# moterdriver.net
KiCad netlist of a schematic drawn in Altium Designer
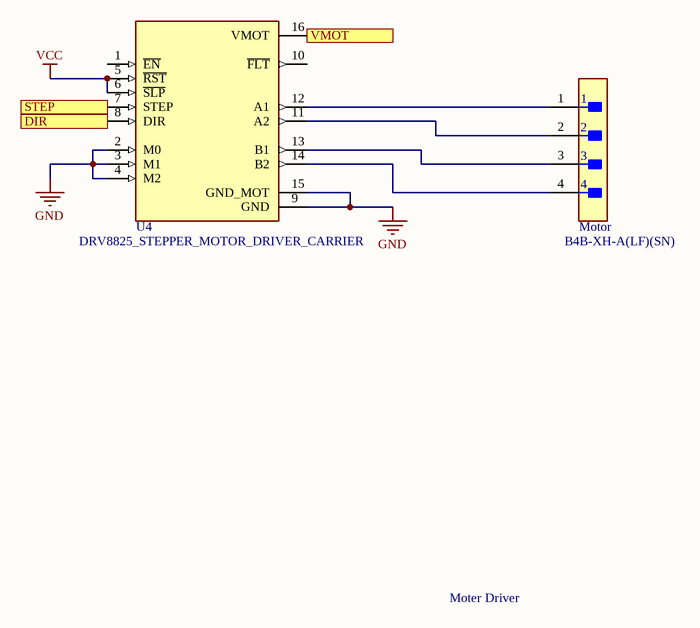
[diagram p0: moterdriver.SchDoc]

(export (version "E")
  (design (tool "Eeschema 10.0.6"))
  (components
    (comp (ref "Motor")
      (value "B4B-XH-A(LF)(SN)")
      (footprint "FP-B4B-XH-A_LF_SN-MFG")
      (description "CONN HEADER VERT 4POS 2.5MM")
      (libsource (lib "Altium Content Vault") (part "299a8cea1bdcbc3624fe62c390fa72c"))
    )
    (comp (ref "U4")
      (value "DRV8825_STEPPER_MOTOR_DRIVER_CARRIER")
      (footprint "IC_DRV8825_STEPPER_MOTOR_DRIVER_CARRIER")
      (description "Stepper motor controler; IC: DRV8825; 1.5A; Uin mot: 8.2Ã·45V")
      (libsource (lib "DRV8825_STEPPER_MOTOR_DRIVER_CARRIER") (part "DRV8825_STEPPER_MOTOR_DRIVER_CARRIER"))
    )
  )
  (nets
    (net (code "1") (name "/DIR") (class "Default")
      (node (ref "U4") (pin "8") (pinfunction "DIR_8") (pintype "input"))
    )
    (net (code "2") (name "/STEP") (class "Default")
      (node (ref "U4") (pin "7") (pinfunction "STEP_7") (pintype "input"))
    )
    (net (code "3") (name "/VMOT") (class "Default")
      (node (ref "U4") (pin "16") (pinfunction "VMOT_16") (pintype "power_in"))
    )
    (net (code "4") (name "GND") (class "Default")
      (node (ref "U4") (pin "15") (pinfunction "GND_MOT_15") (pintype "power_in"))
      (node (ref "U4") (pin "2") (pinfunction "M0_2") (pintype "input"))
      (node (ref "U4") (pin "3") (pinfunction "M1_3") (pintype "input"))
      (node (ref "U4") (pin "4") (pinfunction "M2_4") (pintype "input"))
      (node (ref "U4") (pin "9") (pinfunction "GND_9") (pintype "power_in"))
    )
    (net (code "5") (name "Net-(U4-A1)") (class "Default")
      (node (ref "Motor") (pin "1") (pinfunction "1_1") (pintype "passive"))
      (node (ref "U4") (pin "12") (pinfunction "A1_12") (pintype "output"))
    )
    (net (code "6") (name "Net-(U4-A2)") (class "Default")
      (node (ref "Motor") (pin "2") (pinfunction "2_2") (pintype "passive"))
      (node (ref "U4") (pin "11") (pinfunction "A2_11") (pintype "output"))
    )
    (net (code "7") (name "Net-(U4-B1)") (class "Default")
      (node (ref "Motor") (pin "3") (pinfunction "3_3") (pintype "passive"))
      (node (ref "U4") (pin "13") (pinfunction "B1_13") (pintype "output"))
    )
    (net (code "8") (name "Net-(U4-B2)") (class "Default")
      (node (ref "Motor") (pin "4") (pinfunction "4_4") (pintype "passive"))
      (node (ref "U4") (pin "14") (pinfunction "B2_14") (pintype "output"))
    )
    (net (code "9") (name "VCC") (class "Default")
      (node (ref "U4") (pin "5") (pinfunction "~{RST}_5") (pintype "input"))
      (node (ref "U4") (pin "6") (pinfunction "~{SLP}_6") (pintype "input"))
    )
    (net (code "10") (name "unconnected-(U4-~{EN}-Pad1)") (class "Default")
      (node (ref "U4") (pin "1") (pinfunction "~{EN}_1") (pintype "input"))
    )
    (net (code "11") (name "unconnected-(U4-~{FLT}-Pad10)") (class "Default")
      (node (ref "U4") (pin "10") (pinfunction "~{FLT}_10") (pintype "output"))
    )
  )
)
